# POGO-headers.net
KiCad netlist of a schematic drawn in Altium Designer
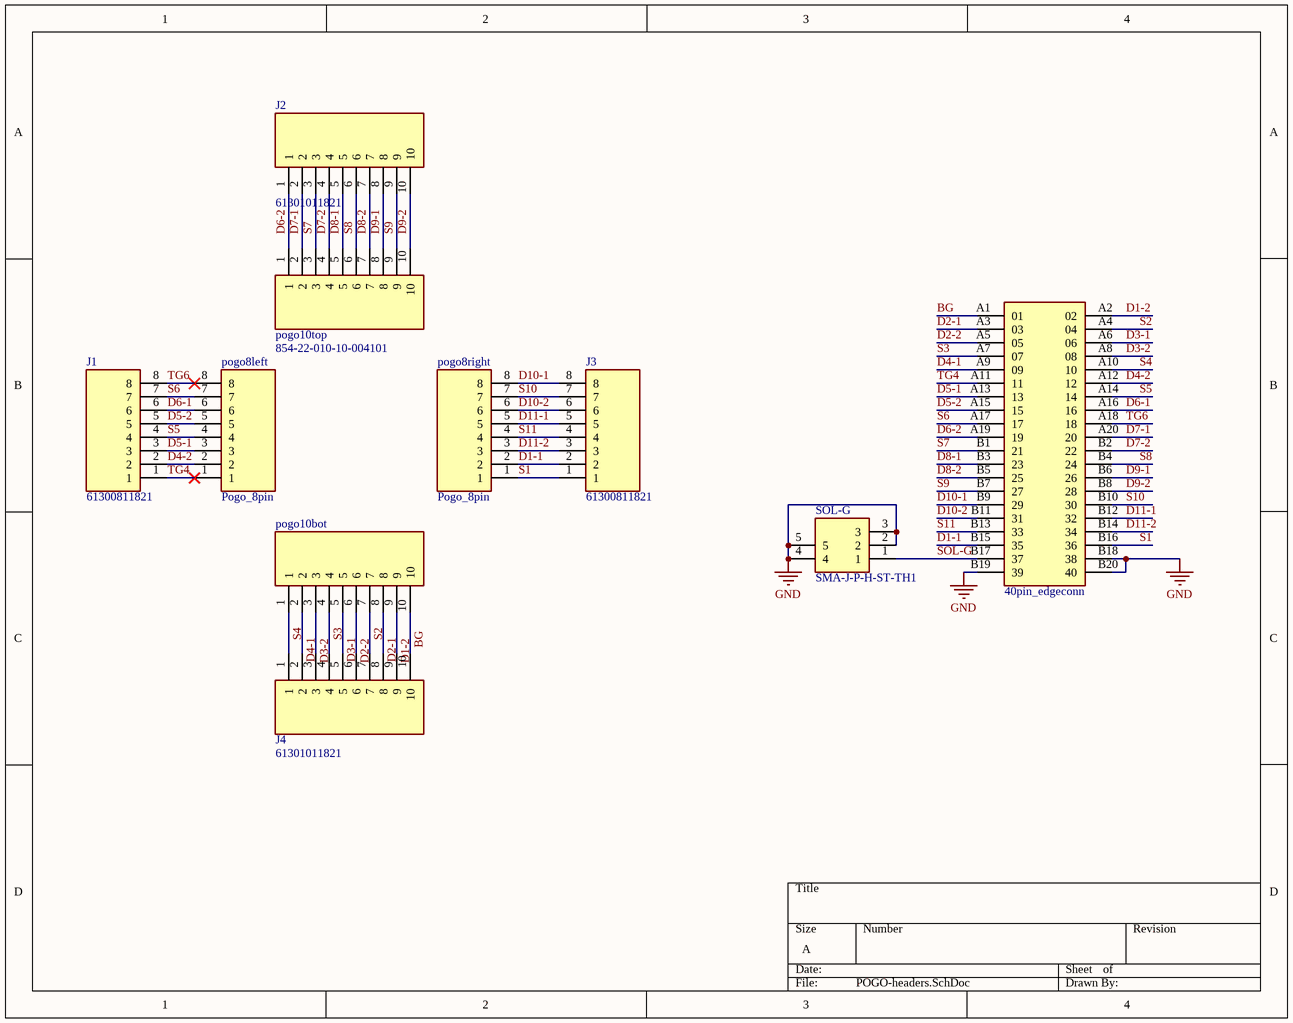
[diagram p0: POGO-headers.SchDoc]

(export (version "E")
  (design (tool "Eeschema 10.0.6"))
  (components
    (comp (ref "CONN")
      (value "40pin_edgeconn")
      (footprint "Edge Connector")
      (libsource (lib "New York University") (part "40pin_edgeconn-Symbol-1"))
    )
    (comp (ref "J1")
      (value "61300811821")
      (footprint "SamacSys:RHDR8W60P0X254_1X8_2082X250X850P")
      (description "Connector")
      (fields (field (name "MOUSER PART NUMBER") "710-61300811821"))
      (libsource (lib "*") (part "61300811821"))
    )
    (comp (ref "J2")
      (value "61301011821")
      (footprint "SamacSys:RHDR10W60P0X254_1X10_2590X250X850P")
      (description "Connector")
      (fields (field (name "MOUSER PART NUMBER") "710-61301011821"))
      (libsource (lib "") (part "61301011821_1"))
    )
    (comp (ref "J3")
      (value "61300811821")
      (footprint "SamacSys:RHDR8W60P0X254_1X8_2082X250X850P")
      (description "Connector")
      (fields (field (name "MOUSER PART NUMBER") "710-61300811821"))
      (libsource (lib "") (part "61300811821_1"))
    )
    (comp (ref "J4")
      (value "61301011821")
      (footprint "SamacSys:RHDR10W60P0X254_1X10_2590X250X850P")
      (description "Connector")
      (fields (field (name "MOUSER PART NUMBER") "710-61301011821"))
      (libsource (lib "*") (part "61301011821"))
    )
    (comp (ref "pogo8left")
      (value "Pogo_8pin")
      (footprint "New footprint 1")
      (description "8-pin pogo pin")
      (libsource (lib "Chengxin Liu") (part "New symbol 1"))
    )
    (comp (ref "pogo8right")
      (value "Pogo_8pin")
      (footprint "New footprint 1")
      (description "8-pin pogo pin")
      (libsource (lib "") (part "New symbol 1_1"))
    )
    (comp (ref "pogo10bot")
      (value "854-22-010-10-004101")
      (footprint "SamacSys:8542201010004101")
      (description "Connector")
      (fields (field (name "MOUSER PART NUMBER") "575-8542201010004101"))
      (libsource (lib "") (part "854-22-010-10-004101_1"))
    )
    (comp (ref "pogo10top")
      (value "854-22-010-10-004101")
      (footprint "SamacSys:8542201010004101")
      (description "Connector")
      (fields (field (name "MOUSER PART NUMBER") "575-8542201010004101"))
      (libsource (lib "8542201010004101") (part "854-22-010-10-004101"))
    )
    (comp (ref "SOL-G")
      (value "SMA-J-P-H-ST-TH1")
      (footprint "SamacSys:SMAJPHSTTH1")
      (description "Connector")
      (fields (field (name "MOUSER PART NUMBER") "200-SMAJPHSTTH1"))
      (libsource (lib "*") (part "SMA-J-P-H-ST-TH1"))
    )
  )
  (nets
    (net (code "1") (name "/BG") (class "Default")
      (node (ref "CONN") (pin "A1") (pinfunction "01_A1") (pintype "passive"))
      (node (ref "J4") (pin "10") (pinfunction "10_10") (pintype "passive"))
      (node (ref "pogo10bot") (pin "10") (pinfunction "10_10") (pintype "passive"))
    )
    (net (code "2") (name "/D1-1") (class "Default")
      (node (ref "CONN") (pin "B15") (pinfunction "35_B15") (pintype "passive"))
      (node (ref "J3") (pin "2") (pinfunction "2_2") (pintype "passive"))
      (node (ref "pogo8right") (pin "2") (pinfunction "2_2") (pintype "passive"))
    )
    (net (code "3") (name "/D1-2") (class "Default")
      (node (ref "CONN") (pin "A2") (pinfunction "02_A2") (pintype "passive"))
      (node (ref "J4") (pin "9") (pinfunction "9_9") (pintype "passive"))
      (node (ref "pogo10bot") (pin "9") (pinfunction "9_9") (pintype "passive"))
    )
    (net (code "4") (name "/D2-1") (class "Default")
      (node (ref "CONN") (pin "A3") (pinfunction "03_A3") (pintype "passive"))
      (node (ref "J4") (pin "8") (pinfunction "8_8") (pintype "passive"))
      (node (ref "pogo10bot") (pin "8") (pinfunction "8_8") (pintype "passive"))
    )
    (net (code "5") (name "/D2-2") (class "Default")
      (node (ref "CONN") (pin "A5") (pinfunction "05_A5") (pintype "passive"))
      (node (ref "J4") (pin "6") (pinfunction "6_6") (pintype "passive"))
      (node (ref "pogo10bot") (pin "6") (pinfunction "6_6") (pintype "passive"))
    )
    (net (code "6") (name "/D3-1") (class "Default")
      (node (ref "CONN") (pin "A6") (pinfunction "06_A6") (pintype "passive"))
      (node (ref "J4") (pin "5") (pinfunction "5_5") (pintype "passive"))
      (node (ref "pogo10bot") (pin "5") (pinfunction "5_5") (pintype "passive"))
    )
    (net (code "7") (name "/D3-2") (class "Default")
      (node (ref "CONN") (pin "A8") (pinfunction "08_A8") (pintype "passive"))
      (node (ref "J4") (pin "3") (pinfunction "3_3") (pintype "passive"))
      (node (ref "pogo10bot") (pin "3") (pinfunction "3_3") (pintype "passive"))
    )
    (net (code "8") (name "/D4-1") (class "Default")
      (node (ref "CONN") (pin "A9") (pinfunction "09_A9") (pintype "passive"))
      (node (ref "J4") (pin "2") (pinfunction "2_2") (pintype "passive"))
      (node (ref "pogo10bot") (pin "2") (pinfunction "2_2") (pintype "passive"))
    )
    (net (code "9") (name "/D4-2") (class "Default")
      (node (ref "CONN") (pin "A12") (pinfunction "12_A12") (pintype "passive"))
      (node (ref "J1") (pin "2") (pinfunction "2_2") (pintype "passive"))
      (node (ref "pogo8left") (pin "2") (pinfunction "2_2") (pintype "passive"))
    )
    (net (code "10") (name "/D5-1") (class "Default")
      (node (ref "CONN") (pin "A13") (pinfunction "13_A13") (pintype "passive"))
      (node (ref "J1") (pin "3") (pinfunction "3_3") (pintype "passive"))
      (node (ref "pogo8left") (pin "3") (pinfunction "3_3") (pintype "passive"))
    )
    (net (code "11") (name "/D5-2") (class "Default")
      (node (ref "CONN") (pin "A15") (pinfunction "15_A15") (pintype "passive"))
      (node (ref "J1") (pin "5") (pinfunction "5_5") (pintype "passive"))
      (node (ref "pogo8left") (pin "5") (pinfunction "5_5") (pintype "passive"))
    )
    (net (code "12") (name "/D6-1") (class "Default")
      (node (ref "CONN") (pin "A16") (pinfunction "16_A16") (pintype "passive"))
      (node (ref "J1") (pin "6") (pinfunction "6_6") (pintype "passive"))
      (node (ref "pogo8left") (pin "6") (pinfunction "6_6") (pintype "passive"))
    )
    (net (code "13") (name "/D6-2") (class "Default")
      (node (ref "CONN") (pin "A19") (pinfunction "19_A19") (pintype "passive"))
      (node (ref "J2") (pin "1") (pinfunction "1_1") (pintype "passive"))
      (node (ref "pogo10top") (pin "1") (pinfunction "1_1") (pintype "passive"))
    )
    (net (code "14") (name "/D7-1") (class "Default")
      (node (ref "CONN") (pin "A20") (pinfunction "20_A20") (pintype "passive"))
      (node (ref "J2") (pin "2") (pinfunction "2_2") (pintype "passive"))
      (node (ref "pogo10top") (pin "2") (pinfunction "2_2") (pintype "passive"))
    )
    (net (code "15") (name "/D7-2") (class "Default")
      (node (ref "CONN") (pin "B2") (pinfunction "22_B2") (pintype "passive"))
      (node (ref "J2") (pin "4") (pinfunction "4_4") (pintype "passive"))
      (node (ref "pogo10top") (pin "4") (pinfunction "4_4") (pintype "passive"))
    )
    (net (code "16") (name "/D8-1") (class "Default")
      (node (ref "CONN") (pin "B3") (pinfunction "23_B3") (pintype "passive"))
      (node (ref "J2") (pin "5") (pinfunction "5_5") (pintype "passive"))
      (node (ref "pogo10top") (pin "5") (pinfunction "5_5") (pintype "passive"))
    )
    (net (code "17") (name "/D8-2") (class "Default")
      (node (ref "CONN") (pin "B5") (pinfunction "25_B5") (pintype "passive"))
      (node (ref "J2") (pin "7") (pinfunction "7_7") (pintype "passive"))
      (node (ref "pogo10top") (pin "7") (pinfunction "7_7") (pintype "passive"))
    )
    (net (code "18") (name "/D9-1") (class "Default")
      (node (ref "CONN") (pin "B6") (pinfunction "26_B6") (pintype "passive"))
      (node (ref "J2") (pin "8") (pinfunction "8_8") (pintype "passive"))
      (node (ref "pogo10top") (pin "8") (pinfunction "8_8") (pintype "passive"))
    )
    (net (code "19") (name "/D9-2") (class "Default")
      (node (ref "CONN") (pin "B8") (pinfunction "28_B8") (pintype "passive"))
      (node (ref "J2") (pin "10") (pinfunction "10_10") (pintype "passive"))
      (node (ref "pogo10top") (pin "10") (pinfunction "10_10") (pintype "passive"))
    )
    (net (code "20") (name "/D10-1") (class "Default")
      (node (ref "CONN") (pin "B9") (pinfunction "29_B9") (pintype "passive"))
      (node (ref "J3") (pin "8") (pinfunction "8_8") (pintype "passive"))
      (node (ref "pogo8right") (pin "8") (pinfunction "8_8") (pintype "passive"))
    )
    (net (code "21") (name "/D10-2") (class "Default")
      (node (ref "CONN") (pin "B11") (pinfunction "31_B11") (pintype "passive"))
      (node (ref "J3") (pin "6") (pinfunction "6_6") (pintype "passive"))
      (node (ref "pogo8right") (pin "6") (pinfunction "6_6") (pintype "passive"))
    )
    (net (code "22") (name "/D11-1") (class "Default")
      (node (ref "CONN") (pin "B12") (pinfunction "32_B12") (pintype "passive"))
      (node (ref "J3") (pin "5") (pinfunction "5_5") (pintype "passive"))
      (node (ref "pogo8right") (pin "5") (pinfunction "5_5") (pintype "passive"))
    )
    (net (code "23") (name "/D11-2") (class "Default")
      (node (ref "CONN") (pin "B14") (pinfunction "34_B14") (pintype "passive"))
      (node (ref "J3") (pin "3") (pinfunction "3_3") (pintype "passive"))
      (node (ref "pogo8right") (pin "3") (pinfunction "3_3") (pintype "passive"))
    )
    (net (code "24") (name "/S1") (class "Default")
      (node (ref "CONN") (pin "B16") (pinfunction "36_B16") (pintype "passive"))
      (node (ref "J3") (pin "1") (pinfunction "1_1") (pintype "passive"))
      (node (ref "pogo8right") (pin "1") (pinfunction "1_1") (pintype "passive"))
    )
    (net (code "25") (name "/S2") (class "Default")
      (node (ref "CONN") (pin "A4") (pinfunction "04_A4") (pintype "passive"))
      (node (ref "J4") (pin "7") (pinfunction "7_7") (pintype "passive"))
      (node (ref "pogo10bot") (pin "7") (pinfunction "7_7") (pintype "passive"))
    )
    (net (code "26") (name "/S3") (class "Default")
      (node (ref "CONN") (pin "A7") (pinfunction "07_A7") (pintype "passive"))
      (node (ref "J4") (pin "4") (pinfunction "4_4") (pintype "passive"))
      (node (ref "pogo10bot") (pin "4") (pinfunction "4_4") (pintype "passive"))
    )
    (net (code "27") (name "/S4") (class "Default")
      (node (ref "CONN") (pin "A10") (pinfunction "10_A10") (pintype "passive"))
      (node (ref "J4") (pin "1") (pinfunction "1_1") (pintype "passive"))
      (node (ref "pogo10bot") (pin "1") (pinfunction "1_1") (pintype "passive"))
    )
    (net (code "28") (name "/S5") (class "Default")
      (node (ref "CONN") (pin "A14") (pinfunction "14_A14") (pintype "passive"))
      (node (ref "J1") (pin "4") (pinfunction "4_4") (pintype "passive"))
      (node (ref "pogo8left") (pin "4") (pinfunction "4_4") (pintype "passive"))
    )
    (net (code "29") (name "/S6") (class "Default")
      (node (ref "CONN") (pin "A17") (pinfunction "17_A17") (pintype "passive"))
      (node (ref "J1") (pin "7") (pinfunction "7_7") (pintype "passive"))
      (node (ref "pogo8left") (pin "7") (pinfunction "7_7") (pintype "passive"))
    )
    (net (code "30") (name "/S7") (class "Default")
      (node (ref "CONN") (pin "B1") (pinfunction "21_B1") (pintype "passive"))
      (node (ref "J2") (pin "3") (pinfunction "3_3") (pintype "passive"))
      (node (ref "pogo10top") (pin "3") (pinfunction "3_3") (pintype "passive"))
    )
    (net (code "31") (name "/S8") (class "Default")
      (node (ref "CONN") (pin "B4") (pinfunction "24_B4") (pintype "passive"))
      (node (ref "J2") (pin "6") (pinfunction "6_6") (pintype "passive"))
      (node (ref "pogo10top") (pin "6") (pinfunction "6_6") (pintype "passive"))
    )
    (net (code "32") (name "/S9") (class "Default")
      (node (ref "CONN") (pin "B7") (pinfunction "27_B7") (pintype "passive"))
      (node (ref "J2") (pin "9") (pinfunction "9_9") (pintype "passive"))
      (node (ref "pogo10top") (pin "9") (pinfunction "9_9") (pintype "passive"))
    )
    (net (code "33") (name "/S10") (class "Default")
      (node (ref "CONN") (pin "B10") (pinfunction "30_B10") (pintype "passive"))
      (node (ref "J3") (pin "7") (pinfunction "7_7") (pintype "passive"))
      (node (ref "pogo8right") (pin "7") (pinfunction "7_7") (pintype "passive"))
    )
    (net (code "34") (name "/S11") (class "Default")
      (node (ref "CONN") (pin "B13") (pinfunction "33_B13") (pintype "passive"))
      (node (ref "J3") (pin "4") (pinfunction "4_4") (pintype "passive"))
      (node (ref "pogo8right") (pin "4") (pinfunction "4_4") (pintype "passive"))
    )
    (net (code "35") (name "/SOL-G") (class "Default")
      (node (ref "CONN") (pin "B17") (pinfunction "37_B17") (pintype "passive"))
      (node (ref "SOL-G") (pin "1") (pinfunction "1_1") (pintype "passive"))
    )
    (net (code "36") (name "/TG4") (class "Default")
      (node (ref "CONN") (pin "A11") (pinfunction "11_A11") (pintype "passive"))
      (node (ref "J1") (pin "1") (pinfunction "1_1") (pintype "passive"))
      (node (ref "pogo8left") (pin "1") (pinfunction "1_1") (pintype "passive"))
    )
    (net (code "37") (name "/TG6") (class "Default")
      (node (ref "CONN") (pin "A18") (pinfunction "18_A18") (pintype "passive"))
      (node (ref "J1") (pin "8") (pinfunction "8_8") (pintype "passive"))
      (node (ref "pogo8left") (pin "8") (pinfunction "8_8") (pintype "passive"))
    )
    (net (code "38") (name "GND") (class "Default")
      (node (ref "CONN") (pin "B18") (pinfunction "38_B18") (pintype "passive"))
      (node (ref "CONN") (pin "B19") (pinfunction "39_B19") (pintype "passive"))
      (node (ref "CONN") (pin "B20") (pinfunction "40_B20") (pintype "passive"))
      (node (ref "SOL-G") (pin "2") (pinfunction "2_2") (pintype "passive"))
      (node (ref "SOL-G") (pin "3") (pinfunction "3_3") (pintype "passive"))
      (node (ref "SOL-G") (pin "4") (pinfunction "4_4") (pintype "passive"))
      (node (ref "SOL-G") (pin "5") (pinfunction "5_5") (pintype "passive"))
    )
  )
)
